# medminds_schdoc.net
KiCad netlist of a schematic drawn in Altium Designer
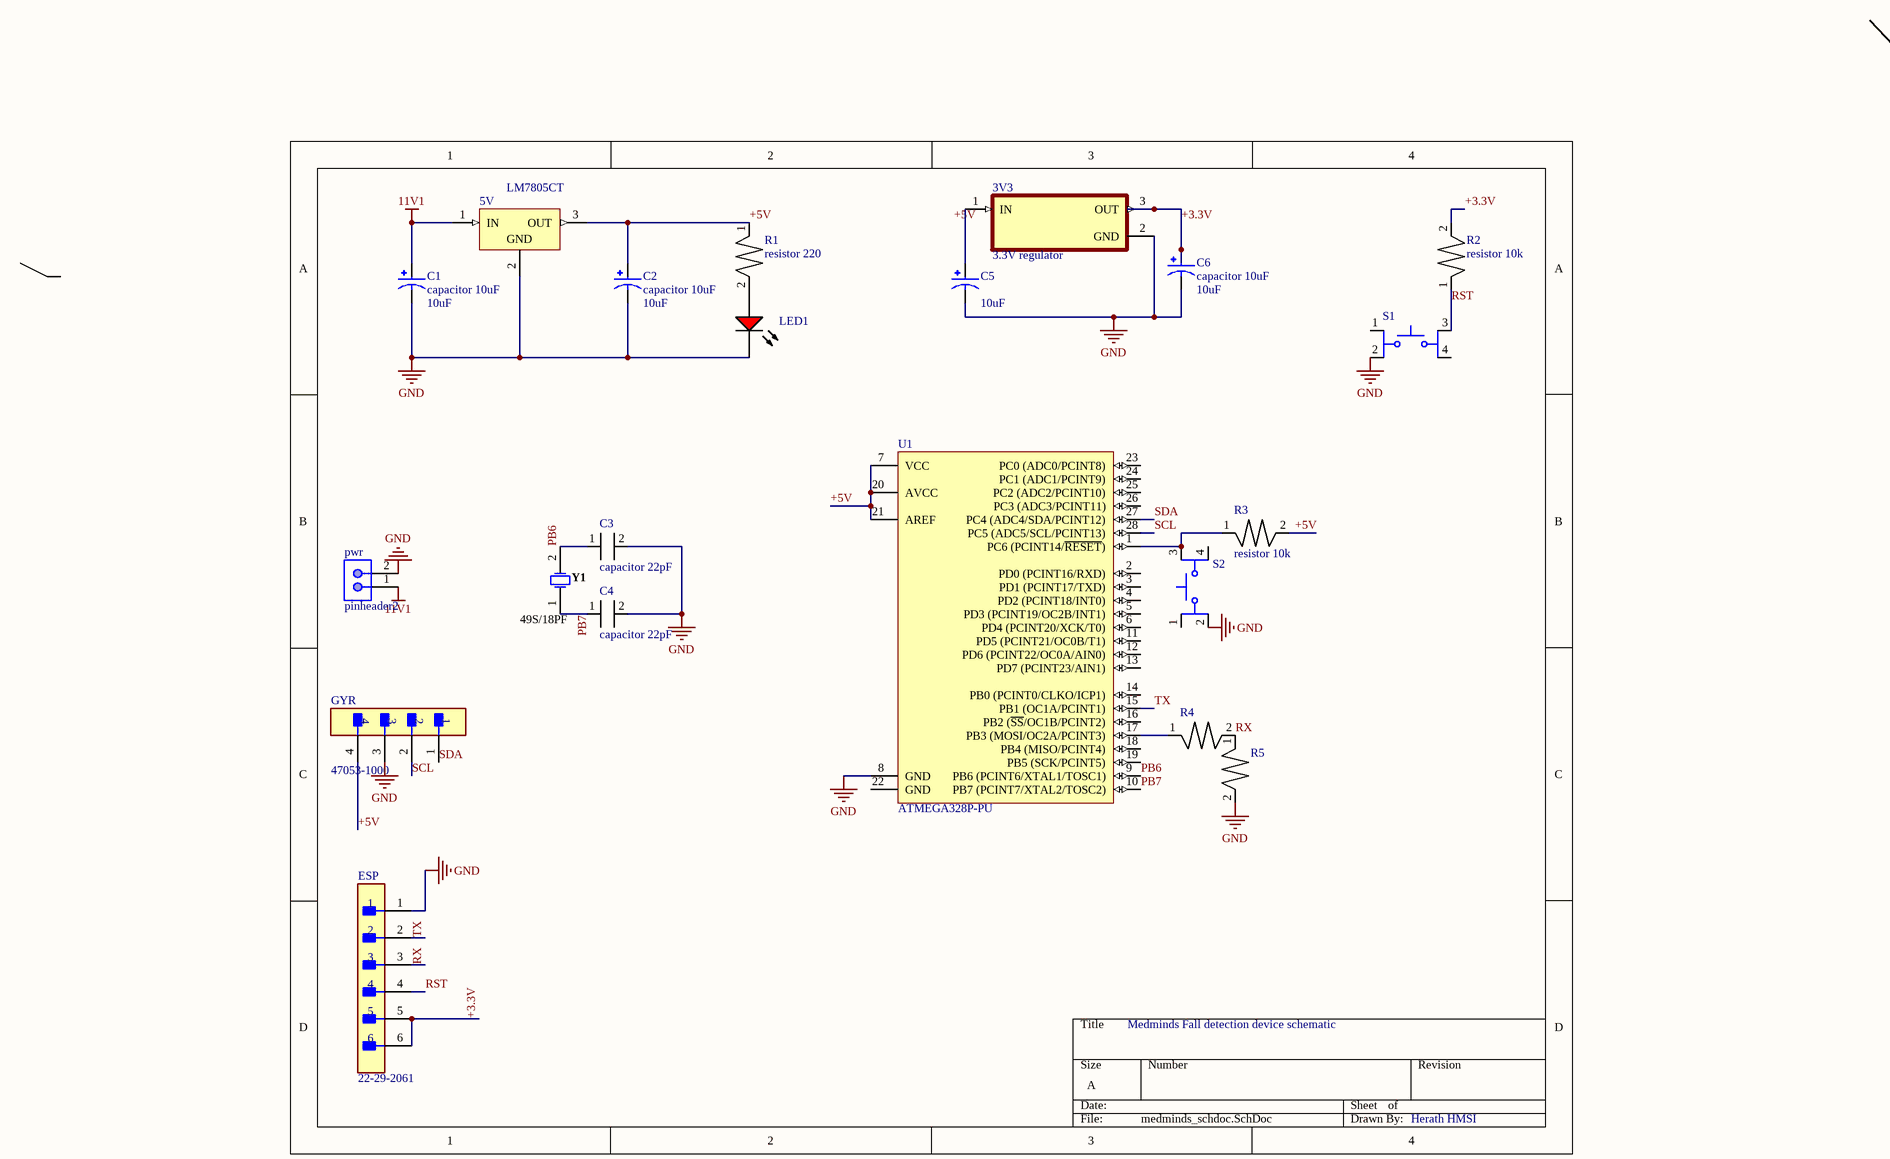
[diagram p0: medminds_schdoc.SchDoc]

(export (version "E")
  (design (tool "Eeschema 10.0.6"))
  (components
    (comp (ref "3V3")
      (value "3.3V regulator")
      (footprint "3.3V regulator")
      (libsource (lib "schematiclib") (part "3.3V regulator"))
    )
    (comp (ref "5V")
      (value "LM7805CT")
      (footprint "FAIR-TO-220-3")
      (description "Fixed Positive Standard Regulator, 5VBIPolar, PSFM3")
      (libsource (lib "herathhmsi 21") (part "FAIR-LM7805CT-TO220-3"))
    )
    (comp (ref "C1")
      (value "capacitor 10uF")
      (footprint "Capacitor10uF")
      (fields
        (field (name "MANUFACTURER") "Panasonic")
        (field (name "MANUFACTURER PART NUMBER") "ECA-1HM100I")
        (field (name "ALTIUM_VALUE") "10uF")
      )
      (libsource (lib "schematiclib") (part "ECA-1HM100I (2)"))
    )
    (comp (ref "C2")
      (value "capacitor 10uF")
      (footprint "Capacitor10uF")
      (fields
        (field (name "MANUFACTURER") "Panasonic")
        (field (name "MANUFACTURER PART NUMBER") "ECA-1HM100I")
        (field (name "ALTIUM_VALUE") "10uF")
      )
      (libsource (lib "schematiclib") (part "ECA-1HM100I (2)"))
    )
    (comp (ref "C3")
      (value "capacitor 22pF")
      (footprint "Capacitor - duplicate")
      (fields
        (field (name "MANUFACTURER") "Murata")
        (field (name "MANUFACTURER PART NUMBER") "DE21XSA220KN3AX02F")
      )
      (libsource (lib "schematiclib") (part "DE21XSA220KN3AX02F"))
    )
    (comp (ref "C4")
      (value "capacitor 22pF")
      (footprint "Capacitor - duplicate")
      (fields
        (field (name "MANUFACTURER") "Murata")
        (field (name "MANUFACTURER PART NUMBER") "DE21XSA220KN3AX02F")
      )
      (libsource (lib "schematiclib") (part "DE21XSA220KN3AX02F"))
    )
    (comp (ref "C5")
      (value "10uF")
      (footprint "Capacitor10uF")
      (fields
        (field (name "MANUFACTURER") "Panasonic")
        (field (name "MANUFACTURER PART NUMBER") "ECA-1HM100I")
        (field (name "Comment") "capacitor 10uF")
      )
      (libsource (lib "schematiclib") (part "ECA-1HM100I (2)"))
    )
    (comp (ref "C6")
      (value "capacitor 10uF")
      (footprint "Capacitor10uF")
      (fields
        (field (name "MANUFACTURER") "Panasonic")
        (field (name "MANUFACTURER PART NUMBER") "ECA-1HM100I")
        (field (name "ALTIUM_VALUE") "10uF")
      )
      (libsource (lib "schematiclib") (part "ECA-1HM100I (2)"))
    )
    (comp (ref "ESP")
      (value "22-29-2061")
      (footprint "FP-22-29-2061-MFG")
      (libsource (lib "schematiclib") (part "22-29-2061"))
    )
    (comp (ref "GYR")
      (value "47053-1000")
      (footprint "FP-47053-1000-MFG")
      (description "CONN HEADER VERT 4POS 2.54MM")
      (libsource (lib "Altium Content Vault") (part "299a8cea1bdcbc3624fe62c390fa72c"))
    )
    (comp (ref "LED1")
      (value "LED1")
      (footprint "INDPR60-254-520X380X650")
      (description "LED Uni-Color Red, 100 mW, 30 mA, -55 to 100 degC, 2-Pin THD, RoHS, Bulk")
      (fields (field (name "MANUFACTURER") "Lite-On"))
      (libsource (lib "herathhmsi 21") (part "LED-RED-AK-2"))
    )
    (comp (ref "pwr")
      (value "pinheader2")
      (footprint "TECO-5-146280-2_V")
      (libsource (lib "schematiclib") (part "pinheader2"))
    )
    (comp (ref "R1")
      (value "resistor 220")
      (footprint "Axial 0.4")
      (description "Fixed Resistor, Carbon Film, 0.25W, 220ohm, 350V, 5% +/-Tol, -400,0ppm/Cel, Through Hole Mount")
      (fields
        (field (name "MANUFACTURER") "Stackpole Electronics")
        (field (name "MANUFACTURER PART NUMBER") "CF14JT220R")
      )
      (libsource (lib "schematiclib") (part "CF14JT220R"))
    )
    (comp (ref "R2")
      (value "resistor 10k")
      (footprint "Axial 0.4")
      (description "Fixed Resistor, Carbon Film, 0.25W, 10000ohm, 350V, 5% +/-Tol, -500,0ppm/Cel, Through Hole Mount")
      (fields
        (field (name "MANUFACTURER") "Stackpole Electronics")
        (field (name "MANUFACTURER PART NUMBER") "CF14JT10K0")
      )
      (libsource (lib "schematiclib") (part "CF14JT10K0"))
    )
    (comp (ref "R3")
      (value "resistor 10k")
      (footprint "Axial 0.4")
      (description "Fixed Resistor, Carbon Film, 0.25W, 10000ohm, 350V, 5% +/-Tol, -500,0ppm/Cel, Through Hole Mount")
      (fields
        (field (name "MANUFACTURER") "Stackpole Electronics")
        (field (name "MANUFACTURER PART NUMBER") "CF14JT10K0")
      )
      (libsource (lib "schematiclib") (part "CF14JT10K0"))
    )
    (comp (ref "R4")
      (value "resistor1k")
      (footprint "Axial 0.4")
      (description "Fixed Resistor, Carbon Film, 0.25W, 1000ohm, 350V, 5% +/-Tol, -400,0ppm/Cel, Through Hole Mount")
      (fields
        (field (name "MANUFACTURER") "Stackpole Electronics")
        (field (name "MANUFACTURER PART NUMBER") "CF14JT1K00")
      )
      (libsource (lib "schematiclib") (part "CF14JT1K00"))
    )
    (comp (ref "R5")
      (value "resistor 2k")
      (footprint "Axial 0.4")
      (description "Res Carbon Film 2K Ohm 5% 1/4W -400ppm/°C to 0ppm/°C Conformal AXL Thru-Hole T/R")
      (fields
        (field (name "MANUFACTURER") "Stackpole Electronics")
        (field (name "MANUFACTURER PART NUMBER") "CF14JT2K00")
      )
      (libsource (lib "schematiclib") (part "CF14JT2K00"))
    )
    (comp (ref "S1")
      (value "tacktile switch")
      (footprint "SW_TL1105AF160Q")
      (fields
        (field (name "MANUFACTURER") "E-Switch")
        (field (name "MANUFACTURER PART NUMBER") "TL1105AF160Q")
      )
      (libsource (lib "schematiclib") (part "TL1105AF160Q"))
    )
    (comp (ref "S2")
      (value "tacktile switch")
      (footprint "SW_TL1105AF160Q")
      (fields
        (field (name "MANUFACTURER") "E-Switch")
        (field (name "MANUFACTURER PART NUMBER") "TL1105AF160Q")
      )
      (libsource (lib "") (part "TL1105AF160Q_1"))
    )
    (comp (ref "U1")
      (value "ATMEGA328P-PU")
      (footprint "ATML-28P3")
      (fields (field (name "MANUFACTURER") "Atmel"))
      (libsource (lib "herathhmsi 21") (part "MC-8B-ATM48-IL28"))
    )
    (comp (ref "Y1")
      (value "49S/18PF")
      (footprint "JPY-49S-18PF")
      (description "Crystal, 16 MHz, +/-20 ppm, 18 pF, -20 to 70 degC, 2-Pin THD, RoHS")
      (fields (field (name "MANUFACTURER") "Shenzhen Jingpengyuan"))
      (libsource (lib "herathhmsi 21") (part "XTAL-1-2-2"))
    )
  )
  (nets
    (net (code "1") (name "/+3.3V") (class "Default")
      (node (ref "3V3") (pin "3") (pinfunction "OUT_3") (pintype "output"))
      (node (ref "C6") (pin "P") (pinfunction "P_P") (pintype "passive"))
      (node (ref "ESP") (pin "5") (pinfunction "5_5") (pintype "passive"))
      (node (ref "ESP") (pin "6") (pinfunction "6_6") (pintype "passive"))
      (node (ref "R2") (pin "2") (pinfunction "2_2") (pintype "passive"))
    )
    (net (code "2") (name "/+5V") (class "Default")
      (node (ref "3V3") (pin "1") (pinfunction "IN_1") (pintype "input"))
      (node (ref "5V") (pin "3") (pinfunction "OUT_3") (pintype "output"))
      (node (ref "C2") (pin "P") (pinfunction "P_P") (pintype "passive"))
      (node (ref "C5") (pin "P") (pinfunction "P_P") (pintype "passive"))
      (node (ref "GYR") (pin "4") (pinfunction "4_4") (pintype "passive"))
      (node (ref "R1") (pin "1") (pinfunction "1_1") (pintype "passive"))
      (node (ref "R3") (pin "2") (pinfunction "2_2") (pintype "passive"))
      (node (ref "U1") (pin "20") (pinfunction "AVCC_20") (pintype "power_in"))
      (node (ref "U1") (pin "21") (pinfunction "AREF_21") (pintype "power_in"))
      (node (ref "U1") (pin "7") (pinfunction "VCC_7") (pintype "power_in"))
    )
    (net (code "3") (name "/PB6") (class "Default")
      (node (ref "C3") (pin "1") (pinfunction "1_1") (pintype "passive"))
      (node (ref "U1") (pin "9") (pinfunction "PB6_(PCINT6/XTAL1/TOSC1)_9") (pintype "bidirectional"))
      (node (ref "Y1") (pin "2") (pinfunction "2_2") (pintype "passive"))
    )
    (net (code "4") (name "/PB7") (class "Default")
      (node (ref "C4") (pin "1") (pinfunction "1_1") (pintype "passive"))
      (node (ref "U1") (pin "10") (pinfunction "PB7_(PCINT7/XTAL2/TOSC2)_10") (pintype "bidirectional"))
      (node (ref "Y1") (pin "1") (pinfunction "1_1") (pintype "passive"))
    )
    (net (code "5") (name "/RST") (class "Default")
      (node (ref "ESP") (pin "4") (pinfunction "4_4") (pintype "passive"))
      (node (ref "R2") (pin "1") (pinfunction "1_1") (pintype "passive"))
      (node (ref "S1") (pin "3") (pinfunction "3_3") (pintype "passive"))
    )
    (net (code "6") (name "/RX") (class "Default")
      (node (ref "ESP") (pin "3") (pinfunction "3_3") (pintype "passive"))
      (node (ref "R4") (pin "2") (pinfunction "2_2") (pintype "passive"))
      (node (ref "R5") (pin "1") (pinfunction "1_1") (pintype "passive"))
    )
    (net (code "7") (name "/SCL") (class "Default")
      (node (ref "GYR") (pin "2") (pinfunction "2_2") (pintype "passive"))
      (node (ref "U1") (pin "28") (pinfunction "PC5_(ADC5/SCL/PCINT13)_28") (pintype "bidirectional"))
    )
    (net (code "8") (name "/SDA") (class "Default")
      (node (ref "GYR") (pin "1") (pinfunction "1_1") (pintype "passive"))
      (node (ref "U1") (pin "27") (pinfunction "PC4_(ADC4/SDA/PCINT12)_27") (pintype "bidirectional"))
    )
    (net (code "9") (name "/TX") (class "Default")
      (node (ref "ESP") (pin "2") (pinfunction "2_2") (pintype "passive"))
      (node (ref "U1") (pin "15") (pinfunction "PB1_(OC1A/PCINT1)_15") (pintype "bidirectional"))
    )
    (net (code "10") (name "11V1") (class "Default")
      (node (ref "5V") (pin "1") (pinfunction "IN_1") (pintype "input"))
      (node (ref "C1") (pin "P") (pinfunction "P_P") (pintype "passive"))
      (node (ref "pwr") (pin "1") (pinfunction "1_1") (pintype "passive"))
    )
    (net (code "11") (name "GND") (class "Default")
      (node (ref "3V3") (pin "2") (pinfunction "GND_2") (pintype "power_in"))
      (node (ref "5V") (pin "2") (pinfunction "GND_2") (pintype "power_in"))
      (node (ref "C1") (pin "N") (pinfunction "N_N") (pintype "passive"))
      (node (ref "C2") (pin "N") (pinfunction "N_N") (pintype "passive"))
      (node (ref "C3") (pin "2") (pinfunction "2_2") (pintype "passive"))
      (node (ref "C4") (pin "2") (pinfunction "2_2") (pintype "passive"))
      (node (ref "C5") (pin "N") (pinfunction "N_N") (pintype "passive"))
      (node (ref "C6") (pin "N") (pinfunction "N_N") (pintype "passive"))
      (node (ref "ESP") (pin "1") (pinfunction "1_1") (pintype "passive"))
      (node (ref "GYR") (pin "3") (pinfunction "3_3") (pintype "passive"))
      (node (ref "LED1") (pin "2") (pinfunction "K_2") (pintype "passive"))
      (node (ref "R5") (pin "2") (pinfunction "2_2") (pintype "passive"))
      (node (ref "S1") (pin "2") (pinfunction "2_2") (pintype "passive"))
      (node (ref "S2") (pin "2") (pinfunction "2_2") (pintype "passive"))
      (node (ref "U1") (pin "8") (pinfunction "GND_8") (pintype "power_in"))
      (node (ref "pwr") (pin "2") (pinfunction "2_2") (pintype "passive"))
    )
    (net (code "12") (name "Net-(LED1-A)") (class "Default")
      (node (ref "LED1") (pin "1") (pinfunction "A_1") (pintype "passive"))
      (node (ref "R1") (pin "2") (pinfunction "2_2") (pintype "passive"))
    )
    (net (code "13") (name "Net-(U1-PB3_(MOSI{slash}OC2A{slash}PCINT3))") (class "Default")
      (node (ref "R4") (pin "1") (pinfunction "1_1") (pintype "passive"))
      (node (ref "U1") (pin "17") (pinfunction "PB3_(MOSI/OC2A/PCINT3)_17") (pintype "bidirectional"))
    )
    (net (code "14") (name "Net-(U1-PC6_(PCINT14{slash}~{RESET}))") (class "Default")
      (node (ref "R3") (pin "1") (pinfunction "1_1") (pintype "passive"))
      (node (ref "S2") (pin "3") (pinfunction "3_3") (pintype "passive"))
      (node (ref "U1") (pin "1") (pinfunction "PC6_(PCINT14/~{RESET})_1") (pintype "bidirectional"))
    )
    (net (code "15") (name "unconnected-(S1-Pad1)") (class "Default")
      (node (ref "S1") (pin "1") (pinfunction "1_1") (pintype "passive"))
    )
    (net (code "16") (name "unconnected-(S1-Pad4)") (class "Default")
      (node (ref "S1") (pin "4") (pinfunction "4_4") (pintype "passive"))
    )
    (net (code "17") (name "unconnected-(S2-Pad1)") (class "Default")
      (node (ref "S2") (pin "1") (pinfunction "1_1") (pintype "passive"))
    )
    (net (code "18") (name "unconnected-(S2-Pad4)") (class "Default")
      (node (ref "S2") (pin "4") (pinfunction "4_4") (pintype "passive"))
    )
    (net (code "19") (name "unconnected-(U1-GND-Pad22)") (class "Default")
      (node (ref "U1") (pin "22") (pinfunction "GND_22") (pintype "power_in"))
    )
    (net (code "20") (name "unconnected-(U1-PB0_(PCINT0{slash}CLKO{slash}ICP1)-Pad14)") (class "Default")
      (node (ref "U1") (pin "14") (pinfunction "PB0_(PCINT0/CLKO/ICP1)_14") (pintype "bidirectional"))
    )
    (net (code "21") (name "unconnected-(U1-PB2_(~{SS}{slash}OC1B{slash}PCINT2)-Pad16)") (class "Default")
      (node (ref "U1") (pin "16") (pinfunction "PB2_(~{SS}/OC1B/PCINT2)_16") (pintype "bidirectional"))
    )
    (net (code "22") (name "unconnected-(U1-PB4_(MISO{slash}PCINT4)-Pad18)") (class "Default")
      (node (ref "U1") (pin "18") (pinfunction "PB4_(MISO/PCINT4)_18") (pintype "bidirectional"))
    )
    (net (code "23") (name "unconnected-(U1-PB5_(SCK{slash}PCINT5)-Pad19)") (class "Default")
      (node (ref "U1") (pin "19") (pinfunction "PB5_(SCK/PCINT5)_19") (pintype "bidirectional"))
    )
    (net (code "24") (name "unconnected-(U1-PC0_(ADC0{slash}PCINT8)-Pad23)") (class "Default")
      (node (ref "U1") (pin "23") (pinfunction "PC0_(ADC0/PCINT8)_23") (pintype "bidirectional"))
    )
    (net (code "25") (name "unconnected-(U1-PC1_(ADC1{slash}PCINT9)-Pad24)") (class "Default")
      (node (ref "U1") (pin "24") (pinfunction "PC1_(ADC1/PCINT9)_24") (pintype "bidirectional"))
    )
    (net (code "26") (name "unconnected-(U1-PC2_(ADC2{slash}PCINT10)-Pad25)") (class "Default")
      (node (ref "U1") (pin "25") (pinfunction "PC2_(ADC2/PCINT10)_25") (pintype "bidirectional"))
    )
    (net (code "27") (name "unconnected-(U1-PC3_(ADC3{slash}PCINT11)-Pad26)") (class "Default")
      (node (ref "U1") (pin "26") (pinfunction "PC3_(ADC3/PCINT11)_26") (pintype "bidirectional"))
    )
    (net (code "28") (name "unconnected-(U1-PD0_(PCINT16{slash}RXD)-Pad2)") (class "Default")
      (node (ref "U1") (pin "2") (pinfunction "PD0_(PCINT16/RXD)_2") (pintype "bidirectional"))
    )
    (net (code "29") (name "unconnected-(U1-PD1_(PCINT17{slash}TXD)-Pad3)") (class "Default")
      (node (ref "U1") (pin "3") (pinfunction "PD1_(PCINT17/TXD)_3") (pintype "bidirectional"))
    )
    (net (code "30") (name "unconnected-(U1-PD2_(PCINT18{slash}INT0)-Pad4)") (class "Default")
      (node (ref "U1") (pin "4") (pinfunction "PD2_(PCINT18/INT0)_4") (pintype "bidirectional"))
    )
    (net (code "31") (name "unconnected-(U1-PD3_(PCINT19{slash}OC2B{slash}INT1)-Pad5)") (class "Default")
      (node (ref "U1") (pin "5") (pinfunction "PD3_(PCINT19/OC2B/INT1)_5") (pintype "bidirectional"))
    )
    (net (code "32") (name "unconnected-(U1-PD4_(PCINT20{slash}XCK{slash}T0)-Pad6)") (class "Default")
      (node (ref "U1") (pin "6") (pinfunction "PD4_(PCINT20/XCK/T0)_6") (pintype "bidirectional"))
    )
    (net (code "33") (name "unconnected-(U1-PD5_(PCINT21{slash}OC0B{slash}T1)-Pad11)") (class "Default")
      (node (ref "U1") (pin "11") (pinfunction "PD5_(PCINT21/OC0B/T1)_11") (pintype "bidirectional"))
    )
    (net (code "34") (name "unconnected-(U1-PD6_(PCINT22{slash}OC0A{slash}AIN0)-Pad12)") (class "Default")
      (node (ref "U1") (pin "12") (pinfunction "PD6_(PCINT22/OC0A/AIN0)_12") (pintype "bidirectional"))
    )
    (net (code "35") (name "unconnected-(U1-PD7_(PCINT23{slash}AIN1)-Pad13)") (class "Default")
      (node (ref "U1") (pin "13") (pinfunction "PD7_(PCINT23/AIN1)_13") (pintype "bidirectional"))
    )
  )
)
